# first.net
KiCad netlist of a schematic drawn in EAGLE
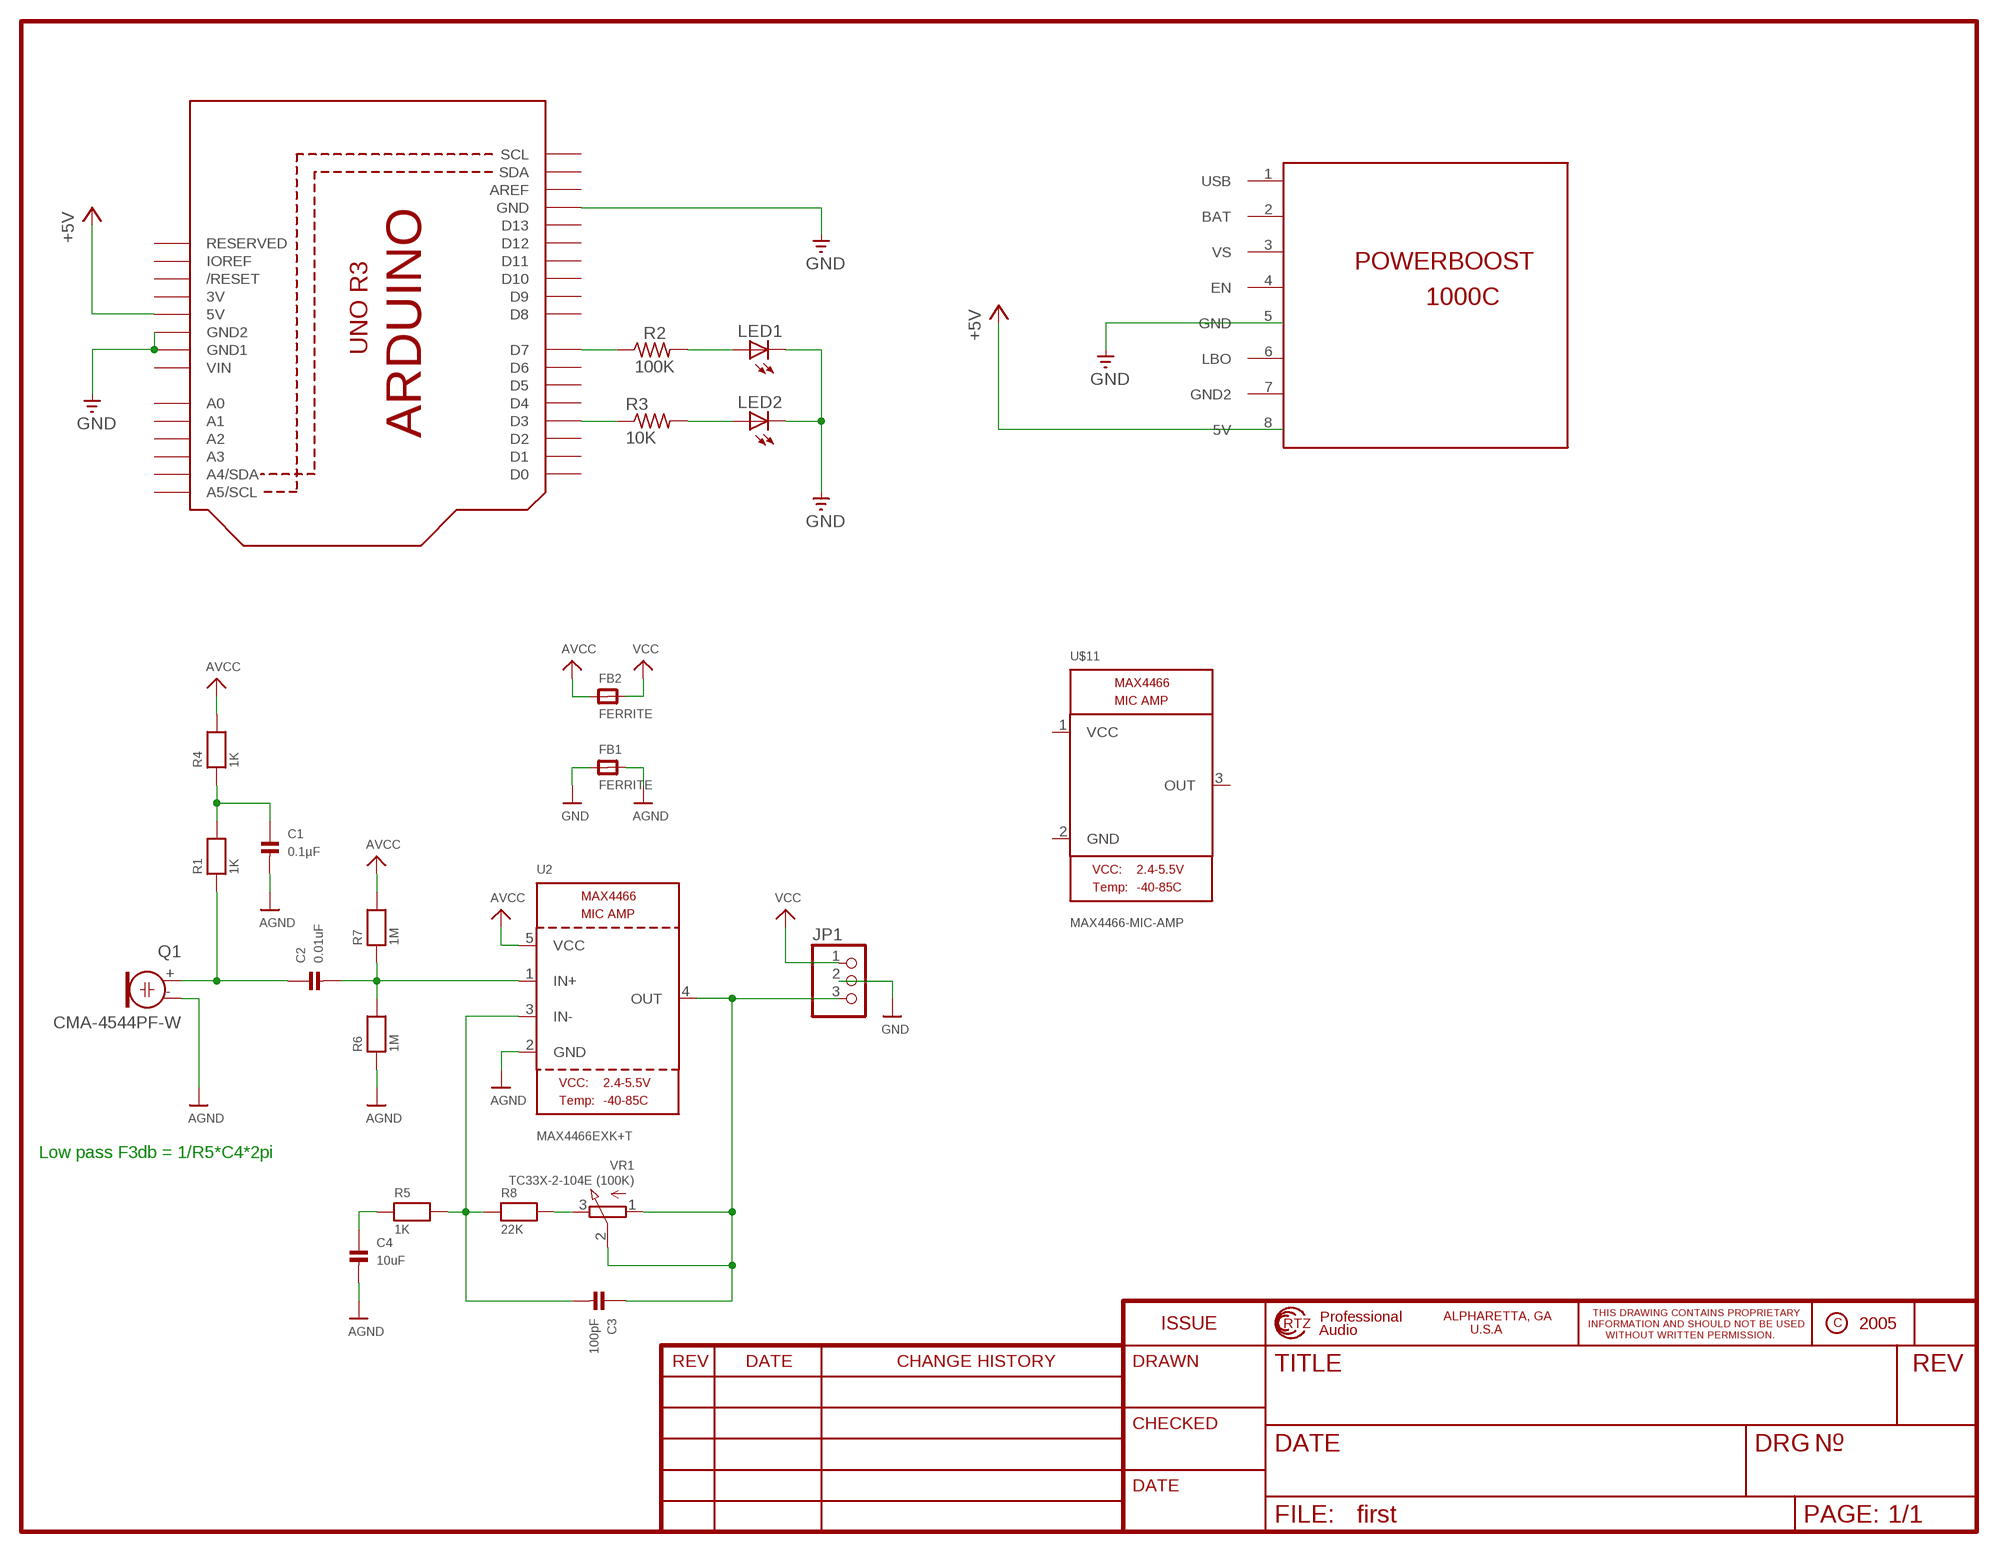
[diagram p0: schematic, sheet 1]

(export (version "E")
  (design (tool "Eeschema 10.0.6"))
  (components
    (comp (ref "C1")
      (value "0.1µF")
      (footprint "eagle-import:0805")
      (libsource (lib "eagle-import") (part "CAP_CERAMIC0805"))
    )
    (comp (ref "C2")
      (value "0.01uF")
      (footprint "eagle-import:0805")
      (libsource (lib "eagle-import") (part "CAP_CERAMIC0805"))
    )
    (comp (ref "C3")
      (value "100pF")
      (footprint "eagle-import:0805")
      (libsource (lib "eagle-import") (part "CAP_CERAMIC0805"))
    )
    (comp (ref "C4")
      (value "10uF")
      (footprint "eagle-import:0805")
      (libsource (lib "eagle-import") (part "CAP_CERAMIC0805"))
    )
    (comp (ref "FB1")
      (value "FERRITE")
      (footprint "eagle-import:0805")
      (libsource (lib "eagle-import") (part "FERRITE0805"))
    )
    (comp (ref "FB2")
      (value "FERRITE")
      (footprint "eagle-import:0805")
      (libsource (lib "eagle-import") (part "FERRITE0805"))
    )
    (comp (ref "JP1")
      (value "HEADER-1X376MIL")
      (footprint "eagle-import:1X03_ROUND_76")
      (libsource (lib "eagle-import") (part "HEADER-1X376MIL"))
    )
    (comp (ref "LED1")
      (value "LED5MM")
      (footprint "eagle-import:LED5MM")
      (libsource (lib "eagle-import") (part "LED5MM"))
    )
    (comp (ref "LED2")
      (value "LED5MM")
      (footprint "eagle-import:LED5MM")
      (libsource (lib "eagle-import") (part "LED5MM"))
    )
    (comp (ref "Q1")
      (value "CMA-4544PF-W")
      (footprint "eagle-import:ELECTRET_9.7")
      (libsource (lib "eagle-import") (part "ELECTRET"))
    )
    (comp (ref "R1")
      (value "1K")
      (footprint "eagle-import:0805")
      (libsource (lib "eagle-import") (part "RESISTOR0805"))
    )
    (comp (ref "R2")
      (value "100K")
      (footprint "eagle-import:0309_10")
      (libsource (lib "eagle-import") (part "R-US_0309/10"))
    )
    (comp (ref "R3")
      (value "10K")
      (footprint "eagle-import:0309_10")
      (libsource (lib "eagle-import") (part "R-US_0309/10"))
    )
    (comp (ref "R4")
      (value "1K")
      (footprint "eagle-import:0805")
      (libsource (lib "eagle-import") (part "RESISTOR0805"))
    )
    (comp (ref "R5")
      (value "1K")
      (footprint "eagle-import:0805")
      (libsource (lib "eagle-import") (part "RESISTOR0805"))
    )
    (comp (ref "R6")
      (value "1M")
      (footprint "eagle-import:0805")
      (libsource (lib "eagle-import") (part "RESISTOR0805"))
    )
    (comp (ref "R7")
      (value "1M")
      (footprint "eagle-import:0805")
      (libsource (lib "eagle-import") (part "RESISTOR0805"))
    )
    (comp (ref "R8")
      (value "22K")
      (footprint "eagle-import:0805")
      (libsource (lib "eagle-import") (part "RESISTOR0805"))
    )
    (comp (ref "U$1")
      (value "ADAFRUIT-POWERBOOST-1000C")
      (footprint "eagle-import:ADAFRUIT-POWERBOOST-1000C")
      (libsource (lib "eagle-import") (part "ADAFRUIT-POWERBOOST-1000C"))
    )
    (comp (ref "U$11")
      (value "MAX4466-MIC-AMP")
      (footprint "eagle-import:MAX4466")
      (libsource (lib "eagle-import") (part "MAX4466-MIC-AMP"))
    )
    (comp (ref "U1")
      (value "ARDUINOR3-BPLACE")
      (footprint "eagle-import:ARDUINOR3-BPLACE")
      (libsource (lib "eagle-import") (part "ARDUINOR3-BPLACE"))
    )
    (comp (ref "U2")
      (value "MAX4466EXK+T")
      (footprint "eagle-import:SC70-5")
      (libsource (lib "eagle-import") (part "MAX4466{dblquote}{dblquote}"))
    )
    (comp (ref "VR1")
      (value "TC33X-2-104E (100K)")
      (footprint "eagle-import:TRIMPOT_BOURNS_TC33X-2")
      (libsource (lib "eagle-import") (part "TRIMPOTTC33X-2"))
    )
  )
  (nets
    (net (code "1") (name "+5V") (class "Default")
      (node (ref "U$1") (pin "8") (pinfunction "5V_8") (pintype "bidirectional"))
      (node (ref "U1") (pin "5V") (pinfunction "5V_5V") (pintype "power_in"))
    )
    (net (code "2") (name "/3V") (class "Default")
      (node (ref "U1") (pin "3V") (pinfunction "3V_3V") (pintype "power_in"))
    )
    (net (code "3") (name "/VIN") (class "Default")
      (node (ref "U1") (pin "VIN") (pinfunction "VIN_VIN") (pintype "power_in"))
    )
    (net (code "4") (name "AGND") (class "Default")
      (node (ref "C1") (pin "2") (pinfunction "P$2_2") (pintype "passive"))
      (node (ref "C4") (pin "2") (pinfunction "P$2_2") (pintype "passive"))
      (node (ref "FB1") (pin "2") (pinfunction "P$2_2") (pintype "passive"))
      (node (ref "Q1") (pin "-") (pinfunction "1_-") (pintype "passive"))
      (node (ref "R6") (pin "1") (pinfunction "1_1") (pintype "passive"))
      (node (ref "U2") (pin "2") (pinfunction "GND_2") (pintype "bidirectional"))
    )
    (net (code "5") (name "AVCC") (class "Default")
      (node (ref "FB2") (pin "1") (pinfunction "P$1_1") (pintype "passive"))
      (node (ref "R4") (pin "2") (pinfunction "2_2") (pintype "passive"))
      (node (ref "R7") (pin "2") (pinfunction "2_2") (pintype "passive"))
      (node (ref "U2") (pin "5") (pinfunction "VCC_5") (pintype "bidirectional"))
    )
    (net (code "6") (name "GND") (class "Default")
      (node (ref "FB1") (pin "1") (pinfunction "P$1_1") (pintype "passive"))
      (node (ref "JP1") (pin "2") (pinfunction "2_2") (pintype "passive"))
      (node (ref "LED1") (pin "K") (pinfunction "C_K") (pintype "passive"))
      (node (ref "LED2") (pin "K") (pinfunction "C_K") (pintype "passive"))
      (node (ref "U$1") (pin "5") (pinfunction "GND_5") (pintype "bidirectional"))
      (node (ref "U1") (pin "GND") (pinfunction "GND_GND") (pintype "power_in"))
      (node (ref "U1") (pin "GND1") (pinfunction "GND1_GND1") (pintype "power_in"))
      (node (ref "U1") (pin "GND2") (pinfunction "GND2_GND2") (pintype "power_in"))
    )
    (net (code "7") (name "Net-(C1-P$1)") (class "Default")
      (node (ref "C1") (pin "1") (pinfunction "P$1_1") (pintype "passive"))
      (node (ref "R1") (pin "2") (pinfunction "2_2") (pintype "passive"))
      (node (ref "R4") (pin "1") (pinfunction "1_1") (pintype "passive"))
    )
    (net (code "8") (name "Net-(C2-P$1)") (class "Default")
      (node (ref "C2") (pin "1") (pinfunction "P$1_1") (pintype "passive"))
      (node (ref "Q1") (pin "+") (pinfunction "2_+") (pintype "passive"))
      (node (ref "R1") (pin "1") (pinfunction "1_1") (pintype "passive"))
    )
    (net (code "9") (name "Net-(C2-P$2)") (class "Default")
      (node (ref "C2") (pin "2") (pinfunction "P$2_2") (pintype "passive"))
      (node (ref "R6") (pin "2") (pinfunction "2_2") (pintype "passive"))
      (node (ref "R7") (pin "1") (pinfunction "1_1") (pintype "passive"))
      (node (ref "U2") (pin "1") (pinfunction "IN+_1") (pintype "bidirectional"))
    )
    (net (code "10") (name "Net-(C3-P$1)") (class "Default")
      (node (ref "C3") (pin "1") (pinfunction "P$1_1") (pintype "passive"))
      (node (ref "JP1") (pin "3") (pinfunction "3_3") (pintype "passive"))
      (node (ref "U2") (pin "4") (pinfunction "OUT_4") (pintype "bidirectional"))
      (node (ref "VR1") (pin "1") (pinfunction "A_1") (pintype "passive"))
      (node (ref "VR1") (pin "2") (pinfunction "S_2") (pintype "passive"))
    )
    (net (code "11") (name "Net-(C3-P$2)") (class "Default")
      (node (ref "C3") (pin "2") (pinfunction "P$2_2") (pintype "passive"))
      (node (ref "R5") (pin "2") (pinfunction "2_2") (pintype "passive"))
      (node (ref "R8") (pin "1") (pinfunction "1_1") (pintype "passive"))
      (node (ref "U2") (pin "3") (pinfunction "IN-_3") (pintype "bidirectional"))
    )
    (net (code "12") (name "Net-(C4-P$1)") (class "Default")
      (node (ref "C4") (pin "1") (pinfunction "P$1_1") (pintype "passive"))
      (node (ref "R5") (pin "1") (pinfunction "1_1") (pintype "passive"))
    )
    (net (code "13") (name "Net-(LED1-PadA)") (class "Default")
      (node (ref "LED1") (pin "A") (pinfunction "A_A") (pintype "passive"))
      (node (ref "R2") (pin "2") (pinfunction "2_2") (pintype "passive"))
    )
    (net (code "14") (name "Net-(LED2-PadA)") (class "Default")
      (node (ref "LED2") (pin "A") (pinfunction "A_A") (pintype "passive"))
      (node (ref "R3") (pin "2") (pinfunction "2_2") (pintype "passive"))
    )
    (net (code "15") (name "Net-(R2-Pad1)") (class "Default")
      (node (ref "R2") (pin "1") (pinfunction "1_1") (pintype "passive"))
      (node (ref "U1") (pin "D7") (pinfunction "D7_D7") (pintype "bidirectional"))
    )
    (net (code "16") (name "Net-(R3-Pad1)") (class "Default")
      (node (ref "R3") (pin "1") (pinfunction "1_1") (pintype "passive"))
      (node (ref "U1") (pin "D3") (pinfunction "D3_D3") (pintype "bidirectional"))
    )
    (net (code "17") (name "Net-(VR1-E)") (class "Default")
      (node (ref "R8") (pin "2") (pinfunction "2_2") (pintype "passive"))
      (node (ref "VR1") (pin "3") (pinfunction "E_3") (pintype "passive"))
    )
    (net (code "18") (name "VCC") (class "Default")
      (node (ref "FB2") (pin "2") (pinfunction "P$2_2") (pintype "passive"))
      (node (ref "JP1") (pin "1") (pinfunction "1_1") (pintype "passive"))
    )
    (net (code "19") (name "unconnected-(U$1-BAT-Pad2)") (class "Default")
      (node (ref "U$1") (pin "2") (pinfunction "BAT_2") (pintype "bidirectional"))
    )
    (net (code "20") (name "unconnected-(U$1-EN-Pad4)") (class "Default")
      (node (ref "U$1") (pin "4") (pinfunction "EN_4") (pintype "bidirectional"))
    )
    (net (code "21") (name "unconnected-(U$1-GND2-Pad7)") (class "Default")
      (node (ref "U$1") (pin "7") (pinfunction "GND2_7") (pintype "bidirectional"))
    )
    (net (code "22") (name "unconnected-(U$1-LBO-Pad6)") (class "Default")
      (node (ref "U$1") (pin "6") (pinfunction "LBO_6") (pintype "bidirectional"))
    )
    (net (code "23") (name "unconnected-(U$1-USB-Pad1)") (class "Default")
      (node (ref "U$1") (pin "1") (pinfunction "USB_1") (pintype "bidirectional"))
    )
    (net (code "24") (name "unconnected-(U$1-VS-Pad3)") (class "Default")
      (node (ref "U$1") (pin "3") (pinfunction "VS_3") (pintype "bidirectional"))
    )
    (net (code "25") (name "unconnected-(U$11-GND-Pad2)") (class "Default")
      (node (ref "U$11") (pin "2") (pinfunction "GND_2") (pintype "bidirectional"))
    )
    (net (code "26") (name "unconnected-(U$11-OUT-Pad3)") (class "Default")
      (node (ref "U$11") (pin "3") (pinfunction "OUT_3") (pintype "bidirectional"))
    )
    (net (code "27") (name "unconnected-(U$11-VCC-Pad1)") (class "Default")
      (node (ref "U$11") (pin "1") (pinfunction "VCC_1") (pintype "bidirectional"))
    )
    (net (code "28") (name "unconnected-(U1-A4{slash}SDA-PadA4)") (class "Default")
      (node (ref "U1") (pin "A4") (pinfunction "A4/SDA_A4") (pintype "bidirectional"))
    )
    (net (code "29") (name "unconnected-(U1-A5{slash}SCL-PadA5)") (class "Default")
      (node (ref "U1") (pin "A5") (pinfunction "A5/SCL_A5") (pintype "bidirectional"))
    )
    (net (code "30") (name "unconnected-(U1-PadA0)") (class "Default")
      (node (ref "U1") (pin "A0") (pinfunction "A0_A0") (pintype "bidirectional"))
    )
    (net (code "31") (name "unconnected-(U1-PadA1)") (class "Default")
      (node (ref "U1") (pin "A1") (pinfunction "A1_A1") (pintype "bidirectional"))
    )
    (net (code "32") (name "unconnected-(U1-PadA2)") (class "Default")
      (node (ref "U1") (pin "A2") (pinfunction "A2_A2") (pintype "bidirectional"))
    )
    (net (code "33") (name "unconnected-(U1-PadA3)") (class "Default")
      (node (ref "U1") (pin "A3") (pinfunction "A3_A3") (pintype "bidirectional"))
    )
    (net (code "34") (name "unconnected-(U1-PadAREF)") (class "Default")
      (node (ref "U1") (pin "AREF") (pinfunction "AREF_AREF") (pintype "bidirectional"))
    )
    (net (code "35") (name "unconnected-(U1-PadD0)") (class "Default")
      (node (ref "U1") (pin "D0") (pinfunction "D0_D0") (pintype "bidirectional"))
    )
    (net (code "36") (name "unconnected-(U1-PadD1)") (class "Default")
      (node (ref "U1") (pin "D1") (pinfunction "D1_D1") (pintype "bidirectional"))
    )
    (net (code "37") (name "unconnected-(U1-PadD2)") (class "Default")
      (node (ref "U1") (pin "D2") (pinfunction "D2_D2") (pintype "bidirectional"))
    )
    (net (code "38") (name "unconnected-(U1-PadD4)") (class "Default")
      (node (ref "U1") (pin "D4") (pinfunction "D4_D4") (pintype "bidirectional"))
    )
    (net (code "39") (name "unconnected-(U1-PadD5)") (class "Default")
      (node (ref "U1") (pin "D5") (pinfunction "D5_D5") (pintype "bidirectional"))
    )
    (net (code "40") (name "unconnected-(U1-PadD6)") (class "Default")
      (node (ref "U1") (pin "D6") (pinfunction "D6_D6") (pintype "bidirectional"))
    )
    (net (code "41") (name "unconnected-(U1-PadD8)") (class "Default")
      (node (ref "U1") (pin "D8") (pinfunction "D8_D8") (pintype "bidirectional"))
    )
    (net (code "42") (name "unconnected-(U1-PadD9)") (class "Default")
      (node (ref "U1") (pin "D9") (pinfunction "D9_D9") (pintype "bidirectional"))
    )
    (net (code "43") (name "unconnected-(U1-PadD10)") (class "Default")
      (node (ref "U1") (pin "D10") (pinfunction "D10_D10") (pintype "bidirectional"))
    )
    (net (code "44") (name "unconnected-(U1-PadD11)") (class "Default")
      (node (ref "U1") (pin "D11") (pinfunction "D11_D11") (pintype "bidirectional"))
    )
    (net (code "45") (name "unconnected-(U1-PadD12)") (class "Default")
      (node (ref "U1") (pin "D12") (pinfunction "D12_D12") (pintype "bidirectional"))
    )
    (net (code "46") (name "unconnected-(U1-PadD13)") (class "Default")
      (node (ref "U1") (pin "D13") (pinfunction "D13_D13") (pintype "bidirectional"))
    )
    (net (code "47") (name "unconnected-(U1-PadIOREF)") (class "Default")
      (node (ref "U1") (pin "IOREF") (pinfunction "IOREF_IOREF") (pintype "output"))
    )
    (net (code "48") (name "unconnected-(U1-PadRESERVED)") (class "Default")
      (node (ref "U1") (pin "RESERVED") (pinfunction "RESERVED_RESERVED") (pintype "no_connect"))
    )
    (net (code "49") (name "unconnected-(U1-PadSCL)") (class "Default")
      (node (ref "U1") (pin "SCL") (pinfunction "SCL_SCL") (pintype "bidirectional"))
    )
    (net (code "50") (name "unconnected-(U1-PadSDA)") (class "Default")
      (node (ref "U1") (pin "SDA") (pinfunction "SDA_SDA") (pintype "bidirectional"))
    )
    (net (code "51") (name "unconnected-(U1-{slash}RESET-PadRESET)") (class "Default")
      (node (ref "U1") (pin "RESET") (pinfunction "/RESET_RESET") (pintype "bidirectional"))
    )
  )
)
